# Communication.net
KiCad netlist of a schematic drawn in Altium Designer
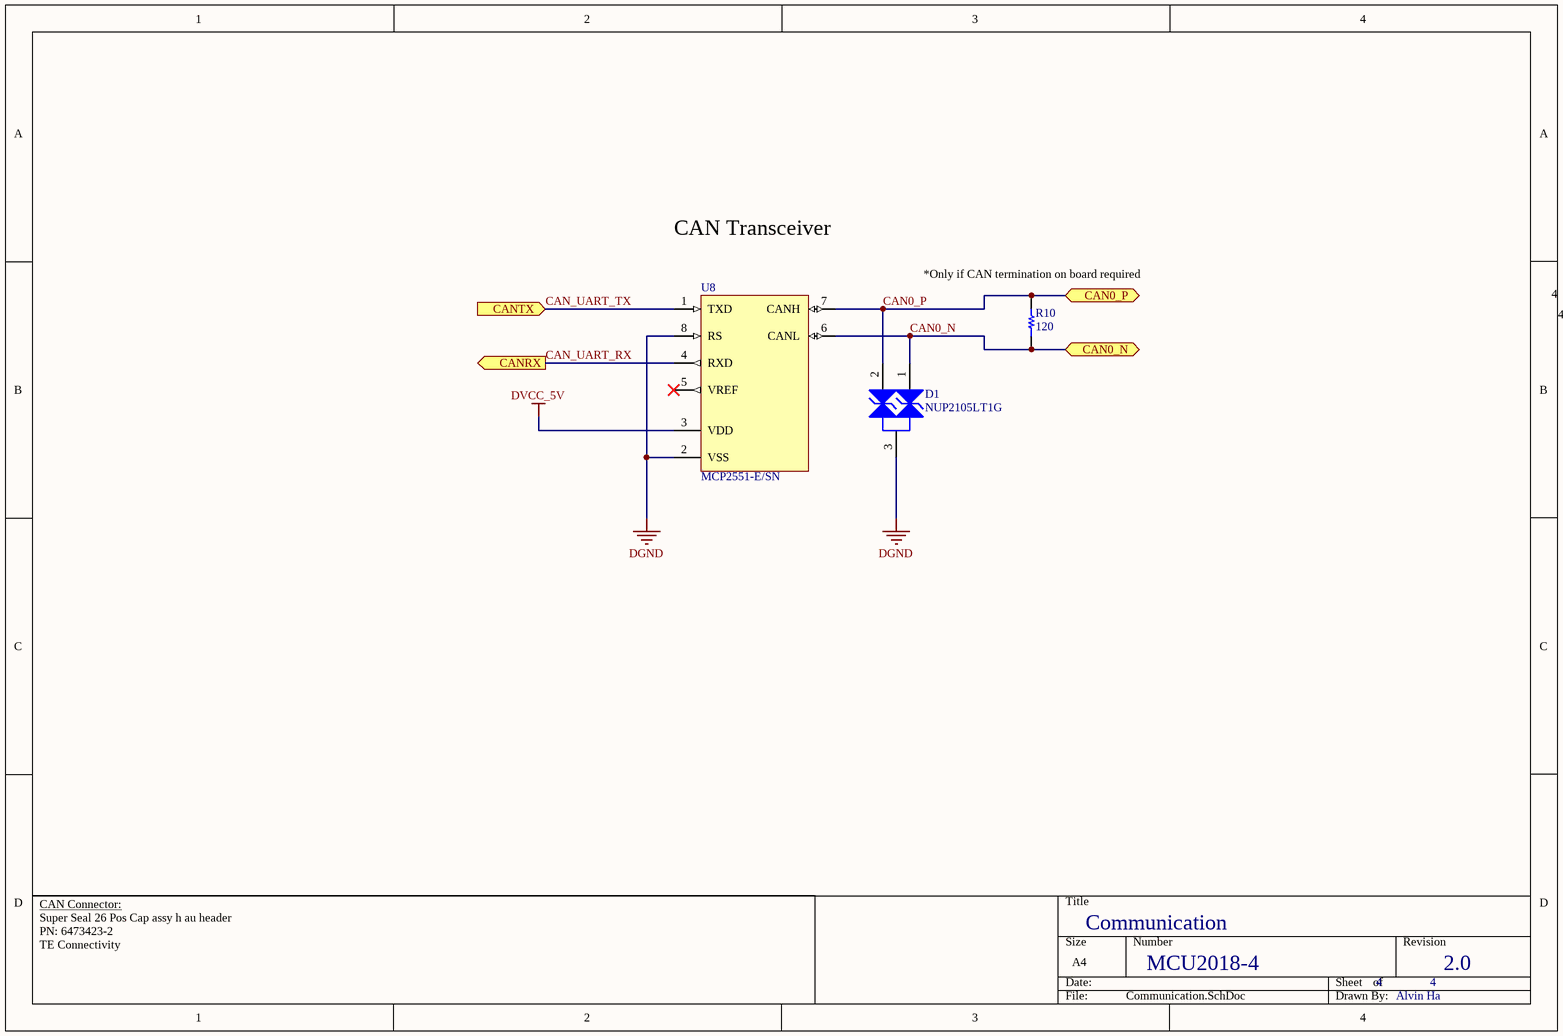
[diagram p0: Communication.SchDoc]

(export (version "E")
  (design (tool "Eeschema 10.0.6"))
  (components
    (comp (ref "D1")
      (value "NUP2105LT1G")
      (footprint "ONSC-SOT-23-3-318-08_V")
      (description "Dual Line CAN Bus Protector, 3-Pin SOT-23, Pb-Free, Tape and Reel")
      (fields (field (name "MANUFACTURER") "On Semiconductor"))
      (libsource (lib "Altium Content Vault") (part "ONSC-NUP21X5X-SOT-23-3-318-08"))
    )
    (comp (ref "R10")
      (value "120")
      (footprint "RES SMT 0805")
      (libsource (lib "Components") (part "Resistor 120 1% 0805"))
    )
    (comp (ref "U8")
      (value "MCP2551-E/SN")
      (footprint "SOIC-SN8_N")
      (description "High-Speed CAN Transceiver, 8-Pin SOIC, Extended Temperature")
      (libsource (lib "Altium Content Vault") (part "COM-TRX-MCP2551-8"))
    )
  )
  (nets
    (net (code "1") (name "/CAN0_N") (class "Default")
      (node (ref "D1") (pin "1") (pinfunction "K_1") (pintype "passive"))
      (node (ref "R10") (pin "1") (pinfunction "1_1") (pintype "passive"))
      (node (ref "U8") (pin "6") (pinfunction "CANL_6") (pintype "bidirectional"))
    )
    (net (code "2") (name "/CAN0_P") (class "Default")
      (node (ref "D1") (pin "2") (pinfunction "K_2") (pintype "passive"))
      (node (ref "R10") (pin "2") (pinfunction "2_2") (pintype "passive"))
      (node (ref "U8") (pin "7") (pinfunction "CANH_7") (pintype "bidirectional"))
    )
    (net (code "3") (name "/CAN_UART_RX") (class "Default")
      (node (ref "U8") (pin "4") (pinfunction "RXD_4") (pintype "output"))
    )
    (net (code "4") (name "/CAN_UART_TX") (class "Default")
      (node (ref "U8") (pin "1") (pinfunction "TXD_1") (pintype "input"))
    )
    (net (code "5") (name "DGND") (class "Default")
      (node (ref "D1") (pin "3") (pinfunction "K_3") (pintype "passive"))
      (node (ref "U8") (pin "2") (pinfunction "VSS_2") (pintype "power_in"))
      (node (ref "U8") (pin "8") (pinfunction "RS_8") (pintype "input"))
    )
    (net (code "6") (name "DVCC_5V") (class "Default")
      (node (ref "U8") (pin "3") (pinfunction "VDD_3") (pintype "power_in"))
    )
    (net (code "7") (name "unconnected-(U8-VREF-Pad5)") (class "Default")
      (node (ref "U8") (pin "5") (pinfunction "VREF_5") (pintype "output+no_connect"))
    )
  )
)
